# Benchtop_Power_Supply.net
KiCad netlist of a schematic drawn in EAGLE
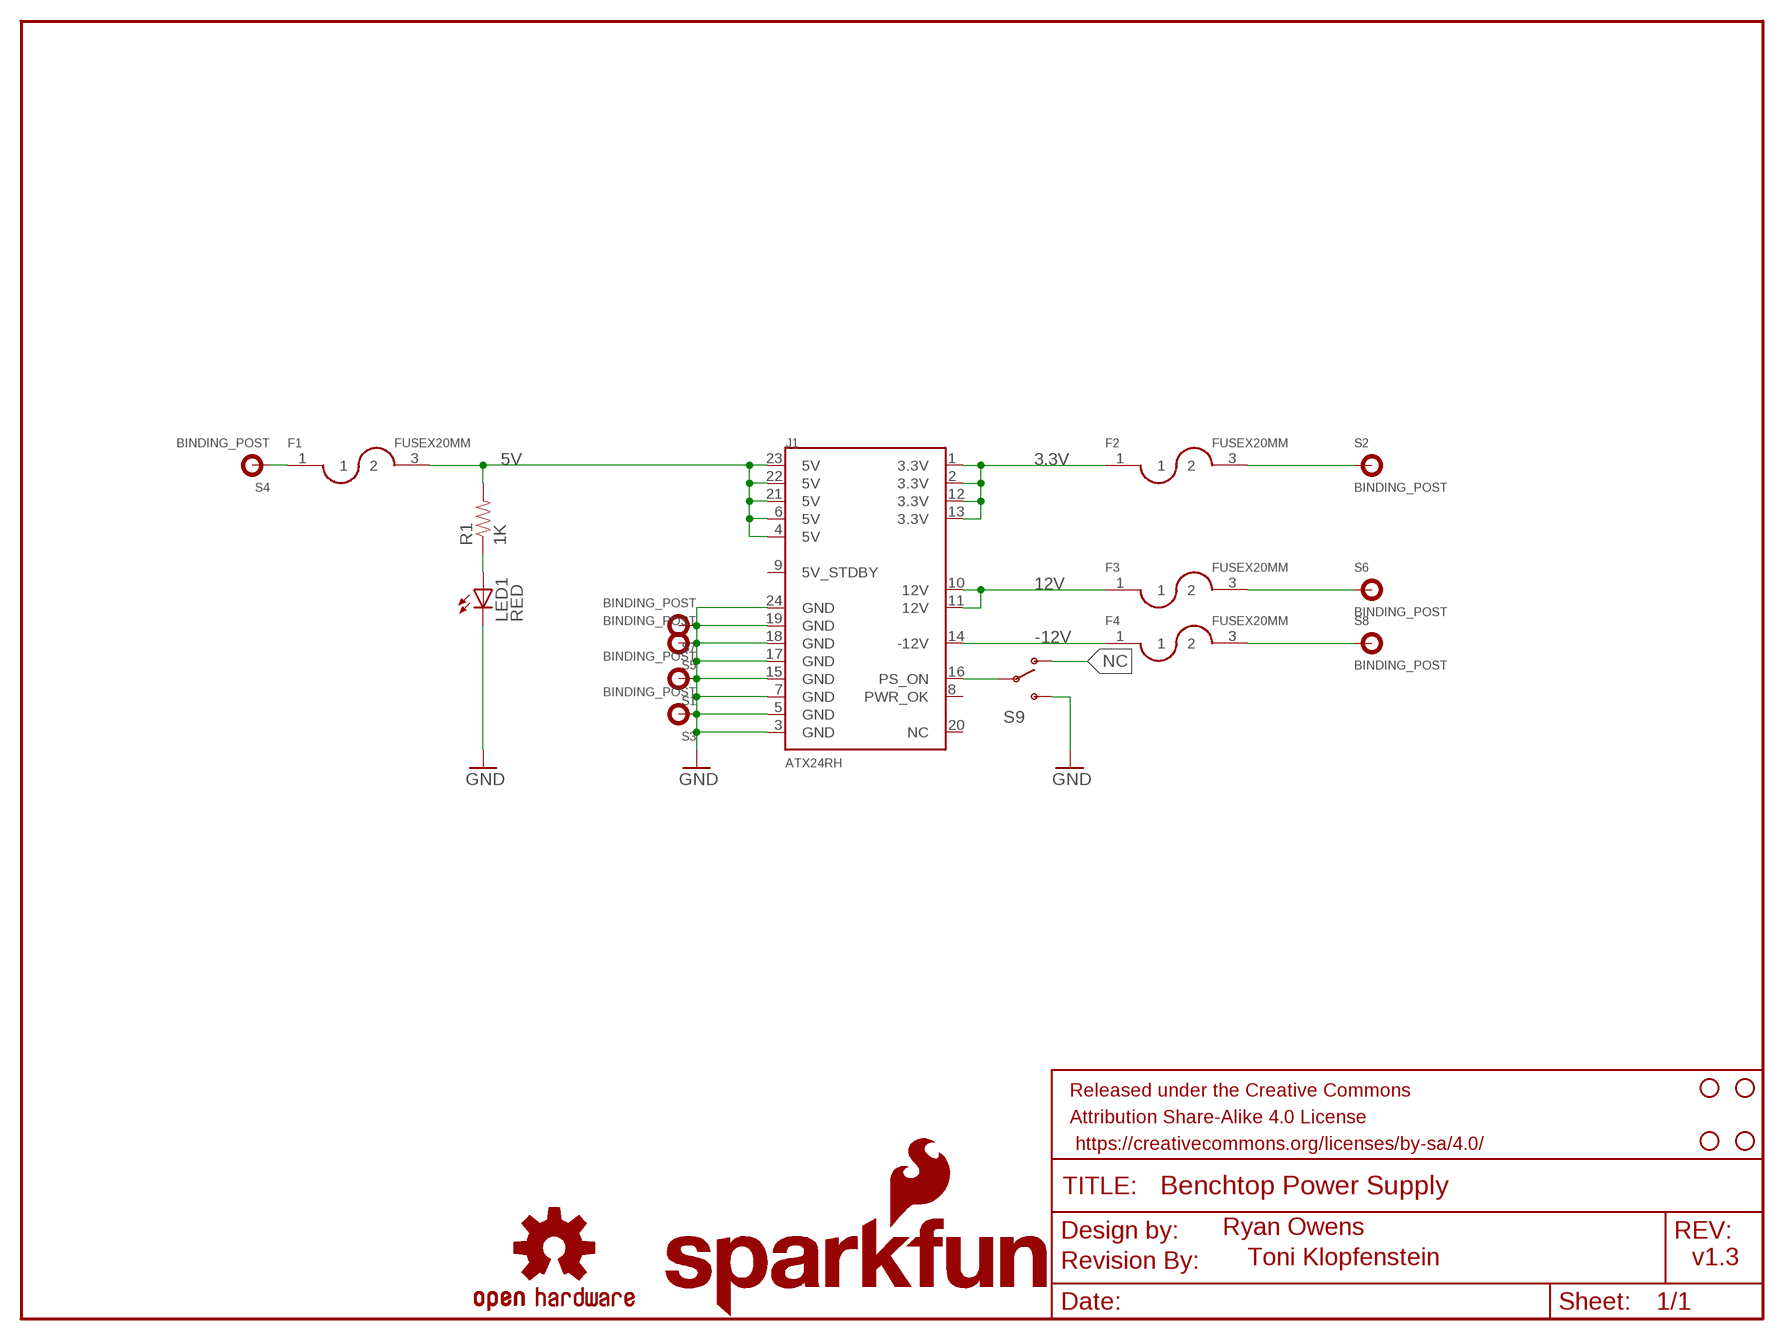
[diagram p0: schematic, sheet 1]

(export (version "E")
  (design (tool "Eeschema 10.0.6"))
  (components
    (comp (ref "F1")
      (value "FUSEX20MM")
      (footprint "eagle-import:FUSE_5MM")
      (libsource (lib "eagle-import") (part "FUSEX20MM"))
    )
    (comp (ref "F2")
      (value "FUSEX20MM")
      (footprint "eagle-import:FUSE_5MM")
      (libsource (lib "eagle-import") (part "FUSEX20MM"))
    )
    (comp (ref "F3")
      (value "FUSEX20MM")
      (footprint "eagle-import:FUSE_5MM")
      (libsource (lib "eagle-import") (part "FUSEX20MM"))
    )
    (comp (ref "F4")
      (value "FUSEX20MM")
      (footprint "eagle-import:FUSE_5MM")
      (libsource (lib "eagle-import") (part "FUSEX20MM"))
    )
    (comp (ref "FRAME1")
      (value "FRAME-LETTER")
      (footprint "eagle-import:CREATIVE_COMMONS")
      (libsource (lib "eagle-import") (part "FRAME-LETTER"))
    )
    (comp (ref "J1")
      (value "ATX24RH")
      (footprint "eagle-import:ATX24_RIGHT_ANGLE")
      (libsource (lib "eagle-import") (part "ATX24RH"))
    )
    (comp (ref "JP1")
      (value "SFE_LOGO_NAME_FLAME.3_INCH")
      (footprint "eagle-import:SFE_LOGO_NAME_FLAME_.3")
      (libsource (lib "eagle-import") (part "SFE_LOGO_NAME_FLAME.3_INCH"))
    )
    (comp (ref "JP2")
      (value "STAND-OFF")
      (footprint "eagle-import:STAND-OFF")
      (libsource (lib "eagle-import") (part "STAND-OFF"))
    )
    (comp (ref "JP3")
      (value "STAND-OFF")
      (footprint "eagle-import:STAND-OFF")
      (libsource (lib "eagle-import") (part "STAND-OFF"))
    )
    (comp (ref "JP4")
      (value "STAND-OFF")
      (footprint "eagle-import:STAND-OFF")
      (libsource (lib "eagle-import") (part "STAND-OFF"))
    )
    (comp (ref "JP5")
      (value "STAND-OFF")
      (footprint "eagle-import:STAND-OFF")
      (libsource (lib "eagle-import") (part "STAND-OFF"))
    )
    (comp (ref "LED1")
      (value "RED")
      (footprint "eagle-import:LED5MM")
      (libsource (lib "eagle-import") (part "LED5MM"))
    )
    (comp (ref "LOGO1")
      (value "OSHW-LOGOL")
      (footprint "eagle-import:OSHW-LOGO-L")
      (libsource (lib "eagle-import") (part "OSHW-LOGOL"))
    )
    (comp (ref "R1")
      (value "1K")
      (footprint "eagle-import:AXIAL-0.3")
      (libsource (lib "eagle-import") (part "RESISTORPTH1"))
    )
    (comp (ref "S1")
      (value "BINDING_POST")
      (footprint "eagle-import:BINDING_POST")
      (libsource (lib "eagle-import") (part "BINDING_POST"))
    )
    (comp (ref "S2")
      (value "BINDING_POST")
      (footprint "eagle-import:BINDING_POST")
      (libsource (lib "eagle-import") (part "BINDING_POST"))
    )
    (comp (ref "S3")
      (value "BINDING_POST")
      (footprint "eagle-import:BINDING_POST")
      (libsource (lib "eagle-import") (part "BINDING_POST"))
    )
    (comp (ref "S4")
      (value "BINDING_POST")
      (footprint "eagle-import:BINDING_POST")
      (libsource (lib "eagle-import") (part "BINDING_POST"))
    )
    (comp (ref "S5")
      (value "BINDING_POST")
      (footprint "eagle-import:BINDING_POST")
      (libsource (lib "eagle-import") (part "BINDING_POST"))
    )
    (comp (ref "S6")
      (value "BINDING_POST")
      (footprint "eagle-import:BINDING_POST")
      (libsource (lib "eagle-import") (part "BINDING_POST"))
    )
    (comp (ref "S7")
      (value "BINDING_POST")
      (footprint "eagle-import:BINDING_POST")
      (libsource (lib "eagle-import") (part "BINDING_POST"))
    )
    (comp (ref "S8")
      (value "BINDING_POST")
      (footprint "eagle-import:BINDING_POST")
      (libsource (lib "eagle-import") (part "BINDING_POST"))
    )
    (comp (ref "S9")
      (value "SWITCH-SPDTKIT")
      (footprint "eagle-import:SWITCH-SPDT_KIT")
      (libsource (lib "eagle-import") (part "SWITCH-SPDTKIT"))
    )
    (comp (ref "U$1")
      (value "REVISION")
      (footprint "eagle-import:REVISION")
      (libsource (lib "eagle-import") (part "REVISION"))
    )
  )
  (nets
    (net (code "1") (name "/-12V") (class "Default")
      (node (ref "F4") (pin "1") (pinfunction "1_1") (pintype "bidirectional"))
      (node (ref "J1") (pin "14") (pinfunction "-12V_14") (pintype "bidirectional"))
    )
    (net (code "2") (name "/3.3V") (class "Default")
      (node (ref "F2") (pin "1") (pinfunction "1_1") (pintype "bidirectional"))
      (node (ref "J1") (pin "1") (pinfunction "3.3V_1") (pintype "bidirectional"))
      (node (ref "J1") (pin "12") (pinfunction "3.3V_12") (pintype "bidirectional"))
      (node (ref "J1") (pin "13") (pinfunction "3.3V_13") (pintype "bidirectional"))
      (node (ref "J1") (pin "2") (pinfunction "3.3V_2") (pintype "bidirectional"))
    )
    (net (code "3") (name "/5V") (class "Default")
      (node (ref "F1") (pin "3") (pinfunction "2_3") (pintype "bidirectional"))
      (node (ref "J1") (pin "21") (pinfunction "5V_21") (pintype "bidirectional"))
      (node (ref "J1") (pin "22") (pinfunction "5V_22") (pintype "bidirectional"))
      (node (ref "J1") (pin "23") (pinfunction "5V_23") (pintype "bidirectional"))
      (node (ref "J1") (pin "4") (pinfunction "5V_4") (pintype "bidirectional"))
      (node (ref "J1") (pin "6") (pinfunction "5V_6") (pintype "bidirectional"))
      (node (ref "R1") (pin "P$2") (pinfunction "2_P$2") (pintype "passive"))
    )
    (net (code "4") (name "/12V") (class "Default")
      (node (ref "F3") (pin "1") (pinfunction "1_1") (pintype "bidirectional"))
      (node (ref "J1") (pin "10") (pinfunction "12V_10") (pintype "bidirectional"))
      (node (ref "J1") (pin "11") (pinfunction "12V_11") (pintype "bidirectional"))
    )
    (net (code "5") (name "GND") (class "Default")
      (node (ref "J1") (pin "15") (pinfunction "GND_15") (pintype "bidirectional"))
      (node (ref "J1") (pin "17") (pinfunction "GND_17") (pintype "bidirectional"))
      (node (ref "J1") (pin "18") (pinfunction "GND_18") (pintype "bidirectional"))
      (node (ref "J1") (pin "19") (pinfunction "GND_19") (pintype "bidirectional"))
      (node (ref "J1") (pin "24") (pinfunction "GND_24") (pintype "bidirectional"))
      (node (ref "J1") (pin "3") (pinfunction "GND_3") (pintype "bidirectional"))
      (node (ref "J1") (pin "5") (pinfunction "GND_5") (pintype "bidirectional"))
      (node (ref "J1") (pin "7") (pinfunction "GND_7") (pintype "bidirectional"))
      (node (ref "LED1") (pin "K") (pinfunction "C_K") (pintype "passive"))
      (node (ref "S1") (pin "P$1") (pinfunction "P$1_P$1") (pintype "bidirectional"))
      (node (ref "S3") (pin "P$1") (pinfunction "P$1_P$1") (pintype "bidirectional"))
      (node (ref "S5") (pin "P$1") (pinfunction "P$1_P$1") (pintype "bidirectional"))
      (node (ref "S7") (pin "P$1") (pinfunction "P$1_P$1") (pintype "bidirectional"))
      (node (ref "S9") (pin "3") (pinfunction "S_3") (pintype "passive"))
    )
    (net (code "6") (name "NC") (class "Default")
      (node (ref "S9") (pin "1") (pinfunction "O_1") (pintype "passive"))
    )
    (net (code "7") (name "Net-(F1-Pad1)") (class "Default")
      (node (ref "F1") (pin "1") (pinfunction "1_1") (pintype "bidirectional"))
      (node (ref "S4") (pin "P$1") (pinfunction "P$1_P$1") (pintype "bidirectional"))
    )
    (net (code "8") (name "Net-(F2-2)") (class "Default")
      (node (ref "F2") (pin "3") (pinfunction "2_3") (pintype "bidirectional"))
      (node (ref "S2") (pin "P$1") (pinfunction "P$1_P$1") (pintype "bidirectional"))
    )
    (net (code "9") (name "Net-(F3-2)") (class "Default")
      (node (ref "F3") (pin "3") (pinfunction "2_3") (pintype "bidirectional"))
      (node (ref "S6") (pin "P$1") (pinfunction "P$1_P$1") (pintype "bidirectional"))
    )
    (net (code "10") (name "Net-(F4-2)") (class "Default")
      (node (ref "F4") (pin "3") (pinfunction "2_3") (pintype "bidirectional"))
      (node (ref "S8") (pin "P$1") (pinfunction "P$1_P$1") (pintype "bidirectional"))
    )
    (net (code "11") (name "Net-(J1-PS_ON)") (class "Default")
      (node (ref "J1") (pin "16") (pinfunction "PS_ON_16") (pintype "bidirectional"))
      (node (ref "S9") (pin "2") (pinfunction "P_2") (pintype "passive"))
    )
    (net (code "12") (name "Net-(R1-1)") (class "Default")
      (node (ref "LED1") (pin "A") (pinfunction "A_A") (pintype "passive"))
      (node (ref "R1") (pin "P$1") (pinfunction "1_P$1") (pintype "passive"))
    )
    (net (code "13") (name "unconnected-(J1-5V_STDBY-Pad9)") (class "Default")
      (node (ref "J1") (pin "9") (pinfunction "5V_STDBY_9") (pintype "bidirectional"))
    )
    (net (code "14") (name "unconnected-(J1-NC-Pad20)") (class "Default")
      (node (ref "J1") (pin "20") (pinfunction "NC_20") (pintype "bidirectional"))
    )
    (net (code "15") (name "unconnected-(J1-PWR_OK-Pad8)") (class "Default")
      (node (ref "J1") (pin "8") (pinfunction "PWR_OK_8") (pintype "bidirectional"))
    )
  )
)
